# Page1.net
KiCad netlist of a schematic drawn in Altium Designer
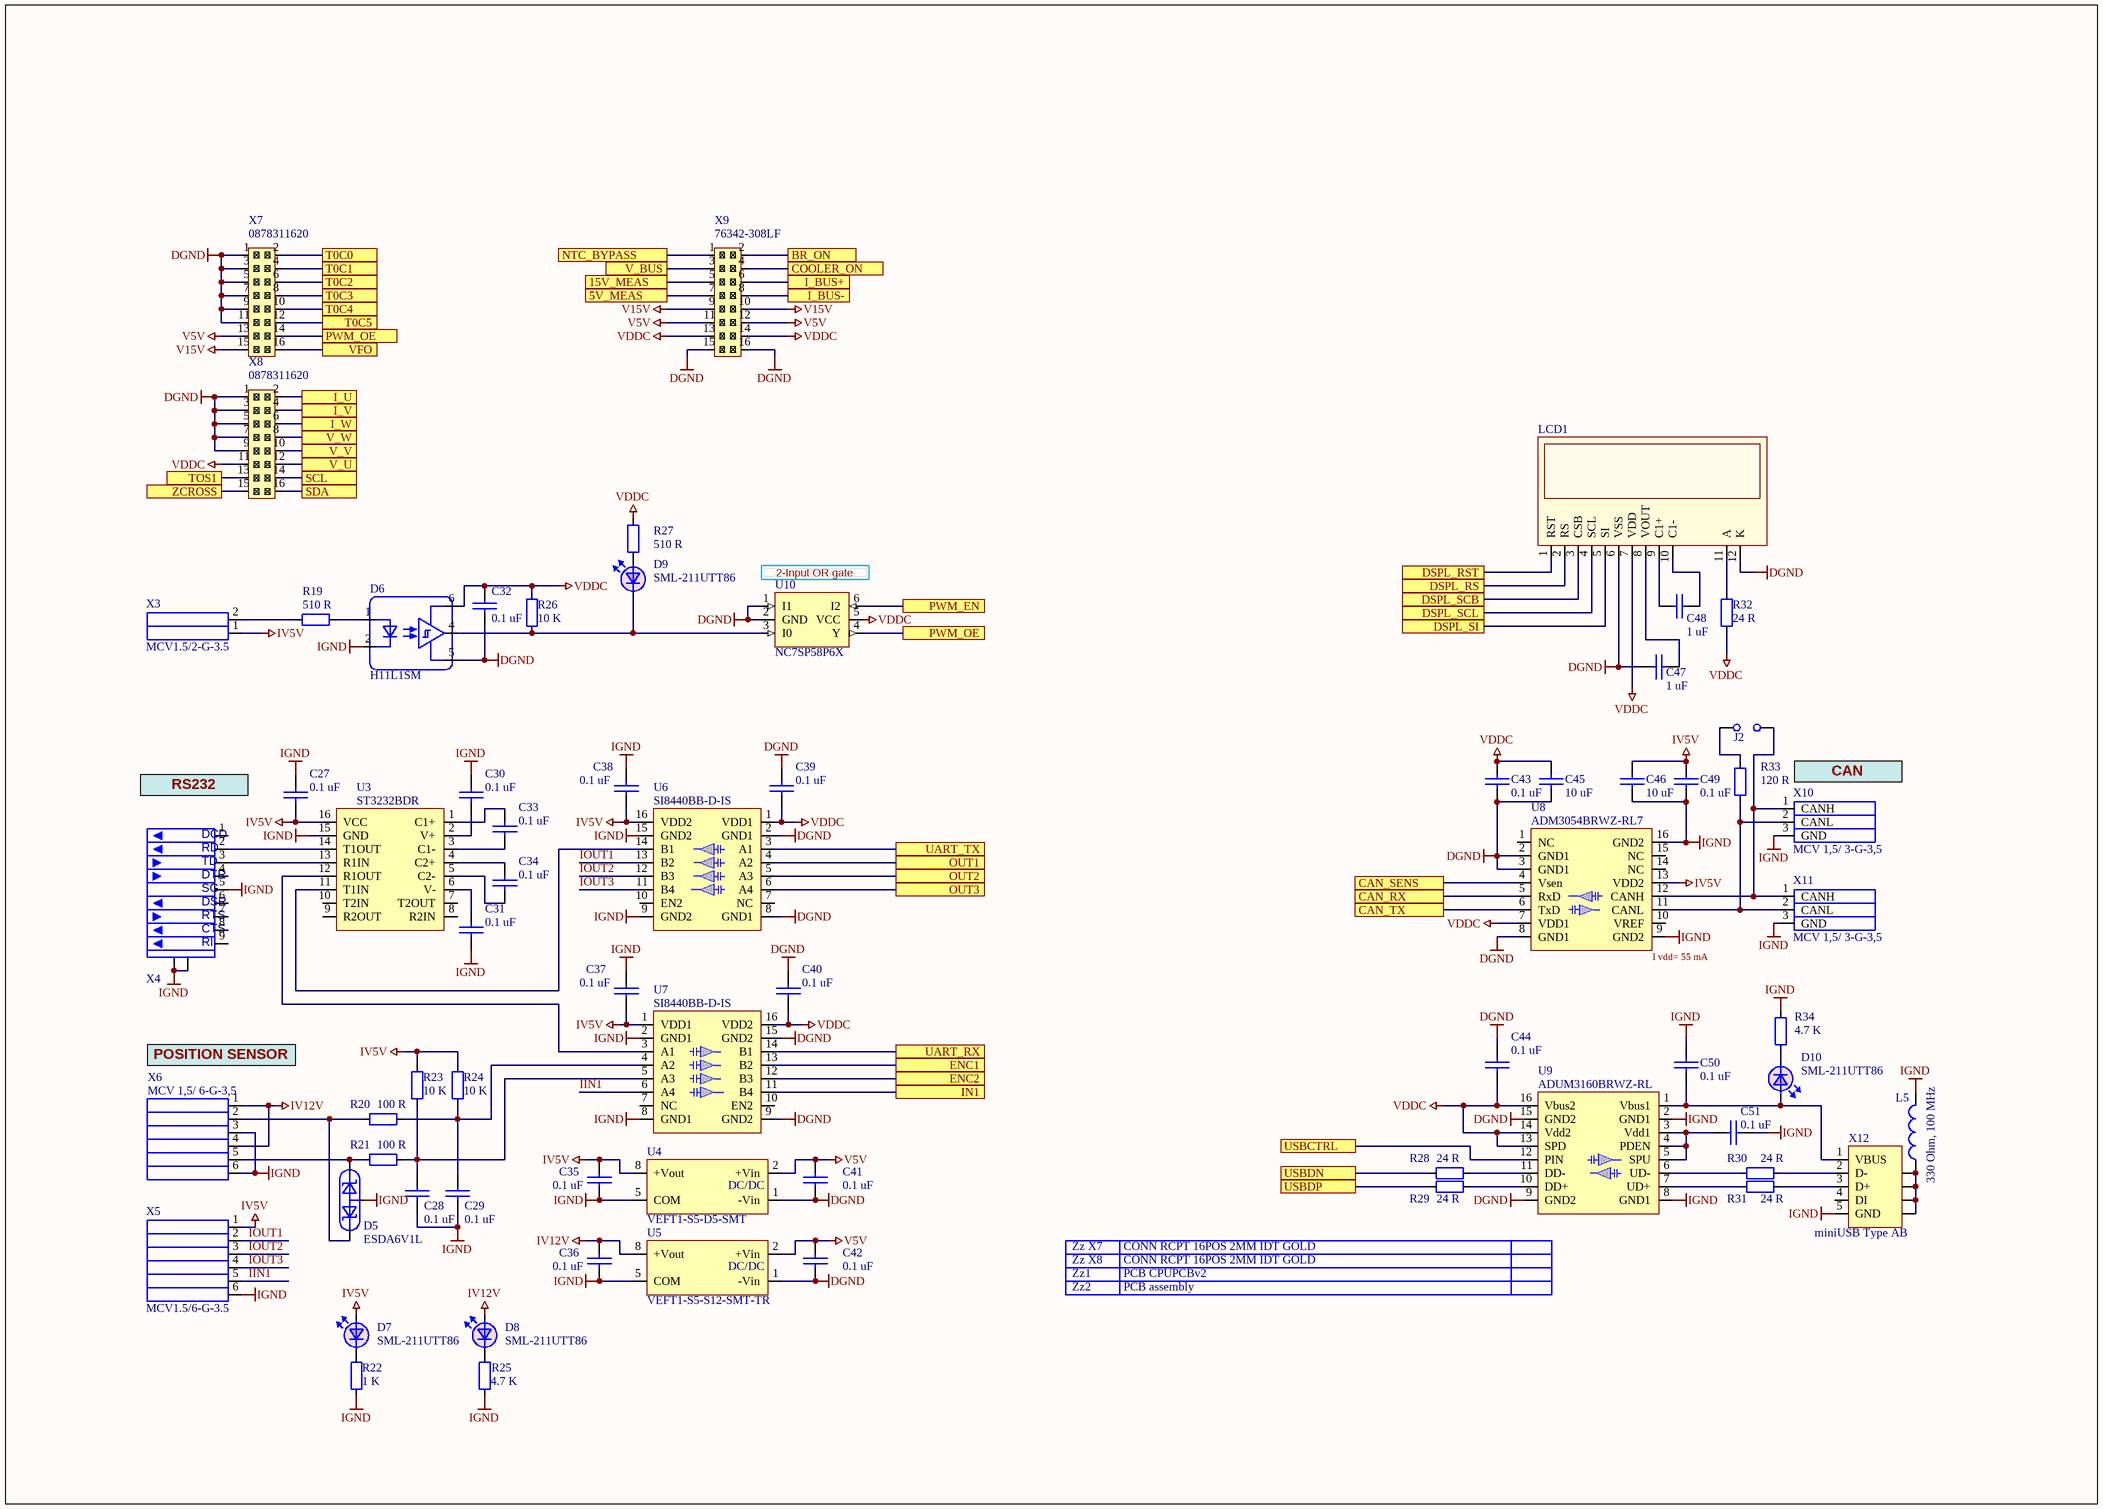
[diagram p0: Page1.SchDoc]

(export (version "E")
  (design (tool "Eeschema 10.0.6"))
  (components
    (comp (ref "C27")
      (value "0.1 uF")
      (footprint "1608[0603]")
      (description "0.1 uF, 25V, 10% , X7R,  0603 SMD MLC Capacitor")
      (fields (field (name "TOLERANCE") "10%") (field (name "MANUFACTURER") "SAMSUNG"))
      (libsource (lib "ea_Capacitors") (part "CVNF100K0603-25"))
    )
    (comp (ref "C28")
      (value "0.1 uF")
      (footprint "1608[0603]")
      (description "0.1 uF, 25V, 10% , X7R,  0603 SMD MLC Capacitor")
      (fields (field (name "TOLERANCE") "10%") (field (name "MANUFACTURER") "SAMSUNG"))
      (libsource (lib "ea_Capacitors") (part "CVNF100K0603-25"))
    )
    (comp (ref "C29")
      (value "0.1 uF")
      (footprint "1608[0603]")
      (description "0.1 uF, 25V, 10% , X7R,  0603 SMD MLC Capacitor")
      (fields (field (name "TOLERANCE") "10%") (field (name "MANUFACTURER") "SAMSUNG"))
      (libsource (lib "ea_Capacitors") (part "CVNF100K0603-25"))
    )
    (comp (ref "C30")
      (value "0.1 uF")
      (footprint "1608[0603]")
      (description "0.1 uF, 25V, 10% , X7R,  0603 SMD MLC Capacitor")
      (fields (field (name "TOLERANCE") "10%") (field (name "MANUFACTURER") "SAMSUNG"))
      (libsource (lib "ea_Capacitors") (part "CVNF100K0603-25"))
    )
    (comp (ref "C31")
      (value "0.1 uF")
      (footprint "1608[0603]")
      (description "0.1 uF, 25V, 10% , X7R,  0603 SMD MLC Capacitor")
      (fields (field (name "TOLERANCE") "10%") (field (name "MANUFACTURER") "SAMSUNG"))
      (libsource (lib "ea_Capacitors") (part "CVNF100K0603-25"))
    )
    (comp (ref "C32")
      (value "0.1 uF")
      (footprint "1608[0603]")
      (description "0.1 uF, 25V, 10% , X7R,  0603 SMD MLC Capacitor")
      (fields (field (name "TOLERANCE") "10%") (field (name "MANUFACTURER") "SAMSUNG"))
      (libsource (lib "ea_Capacitors") (part "CVNF100K0603-25"))
    )
    (comp (ref "C33")
      (value "0.1 uF")
      (footprint "1608[0603]")
      (description "0.1 uF, 25V, 10% , X7R,  0603 SMD MLC Capacitor")
      (fields (field (name "TOLERANCE") "10%") (field (name "MANUFACTURER") "SAMSUNG"))
      (libsource (lib "ea_Capacitors") (part "CVNF100K0603-25"))
    )
    (comp (ref "C34")
      (value "0.1 uF")
      (footprint "1608[0603]")
      (description "0.1 uF, 25V, 10% , X7R,  0603 SMD MLC Capacitor")
      (fields (field (name "TOLERANCE") "10%") (field (name "MANUFACTURER") "SAMSUNG"))
      (libsource (lib "ea_Capacitors") (part "CVNF100K0603-25"))
    )
    (comp (ref "C35")
      (value "0.1 uF")
      (footprint "1608[0603]")
      (description "0.1 uF, 25V, 10% , X7R,  0603 SMD MLC Capacitor")
      (fields (field (name "TOLERANCE") "10%") (field (name "MANUFACTURER") "SAMSUNG"))
      (libsource (lib "ea_Capacitors") (part "CVNF100K0603-25"))
    )
    (comp (ref "C36")
      (value "0.1 uF")
      (footprint "1608[0603]")
      (description "0.1 uF, 25V, 10% , X7R,  0603 SMD MLC Capacitor")
      (fields (field (name "TOLERANCE") "10%") (field (name "MANUFACTURER") "SAMSUNG"))
      (libsource (lib "ea_Capacitors") (part "CVNF100K0603-25"))
    )
    (comp (ref "C37")
      (value "0.1 uF")
      (footprint "1608[0603]")
      (description "0.1 uF, 25V, 10% , X7R,  0603 SMD MLC Capacitor")
      (fields (field (name "TOLERANCE") "10%") (field (name "MANUFACTURER") "SAMSUNG"))
      (libsource (lib "ea_Capacitors") (part "CVNF100K0603-25"))
    )
    (comp (ref "C38")
      (value "0.1 uF")
      (footprint "1608[0603]")
      (description "0.1 uF, 25V, 10% , X7R,  0603 SMD MLC Capacitor")
      (fields (field (name "TOLERANCE") "10%") (field (name "MANUFACTURER") "SAMSUNG"))
      (libsource (lib "ea_Capacitors") (part "CVNF100K0603-25"))
    )
    (comp (ref "C39")
      (value "0.1 uF")
      (footprint "1608[0603]")
      (description "0.1 uF, 25V, 10% , X7R,  0603 SMD MLC Capacitor")
      (fields (field (name "TOLERANCE") "10%") (field (name "MANUFACTURER") "SAMSUNG"))
      (libsource (lib "ea_Capacitors") (part "CVNF100K0603-25"))
    )
    (comp (ref "C40")
      (value "0.1 uF")
      (footprint "1608[0603]")
      (description "0.1 uF, 25V, 10% , X7R,  0603 SMD MLC Capacitor")
      (fields (field (name "TOLERANCE") "10%") (field (name "MANUFACTURER") "SAMSUNG"))
      (libsource (lib "ea_Capacitors") (part "CVNF100K0603-25"))
    )
    (comp (ref "C41")
      (value "0.1 uF")
      (footprint "1608[0603]")
      (description "0.1 uF, 25V, 10% , X7R,  0603 SMD MLC Capacitor")
      (fields (field (name "TOLERANCE") "10%") (field (name "MANUFACTURER") "SAMSUNG"))
      (libsource (lib "ea_Capacitors") (part "CVNF100K0603-25"))
    )
    (comp (ref "C42")
      (value "0.1 uF")
      (footprint "1608[0603]")
      (description "0.1 uF, 25V, 10% , X7R,  0603 SMD MLC Capacitor")
      (fields (field (name "TOLERANCE") "10%") (field (name "MANUFACTURER") "SAMSUNG"))
      (libsource (lib "ea_Capacitors") (part "CVNF100K0603-25"))
    )
    (comp (ref "C43")
      (value "0.1 uF")
      (footprint "1608[0603]")
      (description "0.1 uF, 25V, 10% , X7R,  0603 SMD MLC Capacitor")
      (fields (field (name "TOLERANCE") "10%") (field (name "MANUFACTURER") "SAMSUNG"))
      (libsource (lib "ea_Capacitors") (part "CVNF100K0603-25"))
    )
    (comp (ref "C44")
      (value "0.1 uF")
      (footprint "1608[0603]")
      (description "0.1 uF, 25V, 10% , X7R,  0603 SMD MLC Capacitor")
      (fields (field (name "TOLERANCE") "10%") (field (name "MANUFACTURER") "SAMSUNG"))
      (libsource (lib "ea_Capacitors") (part "CVNF100K0603-25"))
    )
    (comp (ref "C45")
      (value "10 uF")
      (footprint "2012[0805]")
      (description "10 uF, 16V, X5R, ±10%, 0805")
      (fields (field (name "MANUFACTURER") "TDK Corporation") (field (name "TOLERANCE") "±10%"))
      (libsource (lib "ea_Capacitors") (part "C2012X5R1C106K/0.85"))
    )
    (comp (ref "C46")
      (value "10 uF")
      (footprint "2012[0805]")
      (description "10 uF, 16V, X5R, ±10%, 0805")
      (fields (field (name "MANUFACTURER") "TDK Corporation") (field (name "TOLERANCE") "±10%"))
      (libsource (lib "ea_Capacitors") (part "C2012X5R1C106K/0.85"))
    )
    (comp (ref "C47")
      (value "1 uF")
      (footprint "2012[0805]")
      (description "1 uF, 16V, 10%, X7R, 0805")
      (fields (field (name "MANUFACTURER") "Kemet, Rohm, Darfon") (field (name "TOLERANCE") "10%"))
      (libsource (lib "ea_Capacitors") (part "CVUF001K0805"))
    )
    (comp (ref "C48")
      (value "1 uF")
      (footprint "2012[0805]")
      (description "1 uF, 16V, 10%, X7R, 0805")
      (fields (field (name "MANUFACTURER") "Kemet, Rohm, Darfon") (field (name "TOLERANCE") "10%"))
      (libsource (lib "ea_Capacitors") (part "CVUF001K0805"))
    )
    (comp (ref "C49")
      (value "0.1 uF")
      (footprint "1608[0603]")
      (description "0.1 uF, 25V, 10% , X7R,  0603 SMD MLC Capacitor")
      (fields (field (name "TOLERANCE") "10%") (field (name "MANUFACTURER") "SAMSUNG"))
      (libsource (lib "ea_Capacitors") (part "CVNF100K0603-25"))
    )
    (comp (ref "C50")
      (value "0.1 uF")
      (footprint "1608[0603]")
      (description "0.1 uF, 25V, 10% , X7R,  0603 SMD MLC Capacitor")
      (fields (field (name "TOLERANCE") "10%") (field (name "MANUFACTURER") "SAMSUNG"))
      (libsource (lib "ea_Capacitors") (part "CVNF100K0603-25"))
    )
    (comp (ref "C51")
      (value "0.1 uF")
      (footprint "1608[0603]")
      (description "0.1 uF, 25V, 10% , X7R,  0603 SMD MLC Capacitor")
      (fields (field (name "TOLERANCE") "10%") (field (name "MANUFACTURER") "SAMSUNG"))
      (libsource (lib "ea_Capacitors") (part "CVNF100K0603-25"))
    )
    (comp (ref "D5")
      (value "ESDA6V1L")
      (footprint "SOT23")
      (description "Dual transil array for ESD, 6.1 V, 300 W")
      (fields (field (name "MANUFACTURER") "Micro Commercial Co") (field (name "PARTNUM") "ESDA6V1L-TPCT-ND"))
      (libsource (lib "*") (part "ESDA6V1L"))
    )
    (comp (ref "D6")
      (value "H11L1SM")
      (footprint "DIP-6 SMD")
      (description "Optocoupler, SMD, 7500V,  1 Mbit, 1.6 mA")
      (fields
        (field (name "MANUFACTURER") "Fairchild Optoelectronics Group")
        (field (name "PARTNUM") "H11L1SM-ND")
      )
      (libsource (lib "ea_Opto") (part "H11L1SM"))
    )
    (comp (ref "D7")
      (value "SML-211UTT86")
      (footprint "0805 LED")
      (description "0805 red LED, hibright, 2 mA, 1.8V, 130°")
      (fields (field (name "MANUFACTURER") "Rohm") (field (name "PARTNUM") "511-1292-1-ND"))
      (libsource (lib "ea_Indicators") (part "SML-211UTT86"))
    )
    (comp (ref "D8")
      (value "SML-211UTT86")
      (footprint "0805 LED")
      (description "0805 red LED, hibright, 2 mA, 1.8V, 130°")
      (fields (field (name "MANUFACTURER") "Rohm") (field (name "PARTNUM") "511-1292-1-ND"))
      (libsource (lib "ea_Indicators") (part "SML-211UTT86"))
    )
    (comp (ref "D9")
      (value "SML-211UTT86")
      (footprint "0805 LED")
      (description "0805 red LED, hibright, 2 mA, 1.8V, 130°")
      (fields (field (name "MANUFACTURER") "Rohm") (field (name "PARTNUM") "511-1292-1-ND"))
      (libsource (lib "ea_Indicators") (part "SML-211UTT86"))
    )
    (comp (ref "D10")
      (value "SML-211UTT86")
      (footprint "0805 LED")
      (description "0805 red LED, hibright, 2 mA, 1.8V, 130°")
      (fields (field (name "MANUFACTURER") "Rohm") (field (name "PARTNUM") "511-1292-1-ND"))
      (libsource (lib "ea_Indicators") (part "SML-211UTT86"))
    )
    (comp (ref "J2")
      (value "PH1-02-TA-HT")
      (footprint "HDR1X2V")
      (description "2 Pos. 2.54 mm Single Row Through Hole Straight Pin Header")
      (fields (field (name "MANUFACTURER") "ADAM TECH"))
      (libsource (lib "ea_Commutation") (part "Jumper"))
    )
    (comp (ref "L5")
      (value "330 Ohm, 100 MHz")
      (footprint "0603")
      (description "Ferrite bead, 330 Ohm, 100 MHz,  1.5 A, 0.07 Ohm")
      (fields
        (field (name "MANUFACTURER") "Murata Electronics North America")
        (field (name "PARTNUM") "BLM18SG331TN1D")
      )
      (libsource (lib "*") (part "BLM18SG331TN1D"))
    )
    (comp (ref "LCD1")
      (value "NHD-C0216CZ-FSW-FBW-3V3")
      (footprint "Display NHD-C0216CZ-FSW-FBW-3V3")
      (description "LCD COG CHAR 2X16 WHT TRANSFL")
      (fields
        (field (name "MANUFACTURER") "Newhaven Display Intl")
        (field (name "PARTNUM") "NHD-C0216CZ-FSW-FBW-3V3-ND")
      )
      (libsource (lib "ea_LCD") (part "NHD-C0216CZ-FSW-FBW-3V3"))
    )
    (comp (ref "R19")
      (value "510 R")
      (footprint "0603")
      (description "510 R, 1%, 0603, SMD Resistor, Taped")
      (fields (field (name "MANUFACTURER") "Vishay") (field (name "TOLERANCE") "1%"))
      (libsource (lib "ea_Resistors") (part "RL0603E510-1"))
    )
    (comp (ref "R20")
      (value "100 R")
      (footprint "0603")
      (description "100 R, 1%, 0603, SMD Resistor, Taped")
      (fields (field (name "MANUFACTURER") "PANASONIC") (field (name "TOLERANCE") "1%"))
      (libsource (lib "ea_Resistors") (part "RL0603E100-1_1"))
    )
    (comp (ref "R21")
      (value "100 R")
      (footprint "0603")
      (description "100 R, 1%, 0603, SMD Resistor, Taped")
      (fields (field (name "MANUFACTURER") "PANASONIC") (field (name "TOLERANCE") "1%"))
      (libsource (lib "ea_Resistors") (part "RL0603E100-1_1"))
    )
    (comp (ref "R22")
      (value "1 K")
      (footprint "0603")
      (description "1 K, 1%, 0603, SMD Resistor, Taped")
      (fields (field (name "MANUFACTURER") "YAGEO AMERICA CORPORATION") (field (name "TOLERANCE") "1%"))
      (libsource (lib "ea_Resistors") (part "RL0603K001-1_1"))
    )
    (comp (ref "R23")
      (value "10 K")
      (footprint "0603")
      (description "10 K, 1%, 0603, SMD Resistor, Taped")
      (fields (field (name "MANUFACTURER") "PANASONIC") (field (name "TOLERANCE") "1%"))
      (libsource (lib "ea_Resistors") (part "RL0603K010-1"))
    )
    (comp (ref "R24")
      (value "10 K")
      (footprint "0603")
      (description "10 K, 1%, 0603, SMD Resistor, Taped")
      (fields (field (name "MANUFACTURER") "PANASONIC") (field (name "TOLERANCE") "1%"))
      (libsource (lib "ea_Resistors") (part "RL0603K010-1"))
    )
    (comp (ref "R25")
      (value "4.7 K")
      (footprint "0603")
      (description "4.7 K, 1%, 0603, SMD Resistor, Taped")
      (fields (field (name "MANUFACTURER") "YAGEO AMERICA CORPORATION") (field (name "TOLERANCE") "1%"))
      (libsource (lib "ea_Resistors") (part "RL0603K004.7-1_1"))
    )
    (comp (ref "R26")
      (value "10 K")
      (footprint "0603")
      (description "10 K, 1%, 0603, SMD Resistor, Taped")
      (fields (field (name "MANUFACTURER") "PANASONIC") (field (name "TOLERANCE") "1%"))
      (libsource (lib "ea_Resistors") (part "RL0603K010-1"))
    )
    (comp (ref "R27")
      (value "510 R")
      (footprint "0603")
      (description "510 R, 1%, 0603, SMD Resistor, Taped")
      (fields (field (name "MANUFACTURER") "Vishay") (field (name "TOLERANCE") "1%"))
      (libsource (lib "") (part "RL0603E510-1_1"))
    )
    (comp (ref "R28")
      (value "24 R")
      (footprint "0603")
      (description "24 R, 1%, 0603, SMD Resistor, Taped")
      (fields (field (name "MANUFACTURER") "YAGEO AMERICA CORPORATION") (field (name "TOLERANCE") "1%"))
      (libsource (lib "") (part "RL0603E024-1_1_2"))
    )
    (comp (ref "R29")
      (value "24 R")
      (footprint "0603")
      (description "24 R, 1%, 0603, SMD Resistor, Taped")
      (fields (field (name "MANUFACTURER") "YAGEO AMERICA CORPORATION") (field (name "TOLERANCE") "1%"))
      (libsource (lib "") (part "RL0603E024-1_1_1"))
    )
    (comp (ref "R30")
      (value "24 R")
      (footprint "0603")
      (description "24 R, 1%, 0603, SMD Resistor, Taped")
      (fields (field (name "MANUFACTURER") "YAGEO AMERICA CORPORATION") (field (name "TOLERANCE") "1%"))
      (libsource (lib "") (part "RL0603E024-1_1_2"))
    )
    (comp (ref "R31")
      (value "24 R")
      (footprint "0603")
      (description "24 R, 1%, 0603, SMD Resistor, Taped")
      (fields (field (name "MANUFACTURER") "YAGEO AMERICA CORPORATION") (field (name "TOLERANCE") "1%"))
      (libsource (lib "") (part "RL0603E024-1_1_1"))
    )
    (comp (ref "R32")
      (value "24 R")
      (footprint "0603")
      (description "24 R, 1%, 0603, SMD Resistor, Taped")
      (fields (field (name "MANUFACTURER") "YAGEO AMERICA CORPORATION") (field (name "TOLERANCE") "1%"))
      (libsource (lib "ea_Resistors") (part "RL0603E024-1_1"))
    )
    (comp (ref "R33")
      (value "120 R")
      (footprint "0603")
      (description "120 R, 1%, 0603, SMD Resistor, Taped")
      (fields (field (name "MANUFACTURER") "Vishay") (field (name "TOLERANCE") "1%"))
      (libsource (lib "ea_Resistors") (part "RL0603E120-1"))
    )
    (comp (ref "R34")
      (value "4.7 K")
      (footprint "0603")
      (description "4.7 K, 1%, 0603, SMD Resistor, Taped")
      (fields (field (name "MANUFACTURER") "YAGEO AMERICA CORPORATION") (field (name "TOLERANCE") "1%"))
      (libsource (lib "") (part "RL0603K004.7-1_1_1"))
    )
    (comp (ref "U3")
      (value "ST3232BDR")
      (footprint "R-16N, AnalogDev SO-16")
      (description "Low Power, 3.3 V, RS-232 Line Drivers/Receivers, 16-pin TSSOP16")
      (fields (field (name "MANUFACTURER") "ST"))
      (libsource (lib "*") (part "ST3232BDR"))
    )
    (comp (ref "U4")
      (value "VEFT1-S5-D5-SMT")
      (footprint "VEFT1_Sx_Dx_SMT")
      (description "DC/DC 5V In 5V Out,  1W, -40..+85 C, 3KV")
      (fields (field (name "MANUFACTURER") "CUI Inc") (field (name "PARTNUM") "102-2123-1-ND"))
      (libsource (lib "ea_PowerSources") (part "VEFT1-S5-D5-SMT"))
    )
    (comp (ref "U5")
      (value "VEFT1-S5-S12-SMT-TR")
      (footprint "VEFT1_Sx_Dx_SMT")
      (description "DC/DC 5V In 12V Out,  1W, -40..+85 C, 3KV")
      (fields (field (name "MANUFACTURER") "CUI Inc") (field (name "PARTNUM") "102-2132-1-ND"))
      (libsource (lib "ea_PowerSources") (part "VEFT1-S5-S12-SMT-TR"))
    )
    (comp (ref "U6")
      (value "SI8440BB-D-IS")
      (footprint "SO-G16/D10.4")
      (description "IC ISOLATOR 4CH 5.5V 16-SOIC")
      (fields
        (field (name "MANUFACTURER") "Silicon Laboratories Inc")
        (field (name "PARTNUM") "336-1760-5-ND")
      )
      (libsource (lib "ea_IC_Interfaces") (part "SI8440AB-D-IS"))
    )
    (comp (ref "U7")
      (value "SI8440BB-D-IS")
      (footprint "SO-G16/D10.4")
      (description "IC ISOLATOR 4CH 5.5V 16-SOIC")
      (fields
        (field (name "MANUFACTURER") "Silicon Laboratories Inc")
        (field (name "PARTNUM") "336-1760-5-ND")
      )
      (libsource (lib "") (part "SI8440AB-D-IS_1"))
    )
    (comp (ref "U8")
      (value "ADM3054BRWZ-RL7")
      (footprint "SO-G16/D10.4")
      (description "IC Isol TXRX CAN HS 16SOIC")
      (fields (field (name "MANUFACTURER") "Analog Divices") (field (name "PARTNUM") "ADM3054BRWZ-RL7CT-ND"))
      (libsource (lib "ea_IC_Interfaces") (part "ADM3054BRWZ-RL7"))
    )
    (comp (ref "U9")
      (value "ADUM3160BRWZ-RL")
      (footprint "SO-G16/D10.4")
      (description "IC Isol USB 2.5K 16SOIC")
      (fields (field (name "MANUFACTURER") "Analog Divices") (field (name "PARTNUM") "ADUM3160BRWZ-RLCT-ND"))
      (libsource (lib "ea_IC_Interfaces") (part "ADUM3160BRWZ-RL"))
    )
    (comp (ref "U10")
      (value "NC7SP58P6X")
      (footprint "SOT363")
      (description "IC GATE ULP UNIV 2-INP SOT363")
      (fields (field (name "MANUFACTURER") "TEXAS INSTRUMENTS") (field (name "PARTNUM") "NC7SP58P6XCT-ND"))
      (libsource (lib "ea_IC_Logic") (part "NC7SP58P6X"))
    )
    (comp (ref "X3")
      (value "MCV1.5/2-G-3.5")
      (footprint "mcv1.5-2-g_3.5")
      (description "HEADER, VERTICAL, 3.5MM, 2WAY")
      (fields (field (name "MANUFACTURER") "PHOENIX CONTACT") (field (name "PARTNUM") "3704816"))
      (libsource (lib "ea_Connectors") (part "MCV1.5/2-G-3.5"))
    )
    (comp (ref "X4")
      (value "DB9V_1-1634222-2")
      (footprint "DB9 vertical")
      (description "AMP - 1-1634222-2 - SOCKET, D, PCB, THR/INSERT, 9WAY")
      (fields (field (name "MANUFACTURER") "TYCO ELECTRONICS / AMP") (field (name "PARTNUM") "5082018"))
      (libsource (lib "ea_Connectors") (part "DB9V_1-1634222-2"))
    )
    (comp (ref "X5")
      (value "MCV1.5/6-G-3.5")
      (footprint "mcv1.5-6-g_3.5")
      (description "HEADER, VERTICAL, 3.5MM, 6WAY")
      (fields (field (name "MANUFACTURER") "PHOENIX CONTACT") (field (name "PARTNUM") "3704853"))
      (libsource (lib "ea_Connectors") (part "MCV1.5/6-G-3.5"))
    )
    (comp (ref "X6")
      (value "MCV 1,5/ 6-G-3,5")
      (footprint "mcv1.5-6-g_3.5")
      (description "HEADER, VERTICAL, 3.5MM, 6WAY")
      (fields (field (name "MANUFACTURER") "PHOENIX CONTACT") (field (name "PARTNUM") "1843648"))
      (libsource (lib "ea_Connectors") (part "MCV1.5/6-G-3.5"))
    )
    (comp (ref "X7")
      (value "0878311620")
      (footprint "8x2, 2.00mm Pitch Milli-Grid™ Header, Molex")
      (description "CONN HEADER 16POS 2MM VERT GOLD")
      (fields (field (name "MANUFACTURER") "Molex") (field (name "PARTNUM") "WM18562-ND"))
      (libsource (lib "ea_Connectors") (part "0878311620"))
    )
    (comp (ref "X8")
      (value "0878311620")
      (footprint "8x2, 2.00mm Pitch Milli-Grid™ Header, Molex")
      (description "CONN HEADER 16POS 2MM VERT GOLD")
      (fields (field (name "MANUFACTURER") "Molex") (field (name "PARTNUM") "WM18562-ND"))
      (libsource (lib "ea_Connectors") (part "0878311620"))
    )
    (comp (ref "X9")
      (value "76342-308LF")
      (footprint "76342-308LF")
      (description "Board to Board & Mezzanine Connectors 16P VRT DR RECEPT .76 GOLD")
      (fields (field (name "MANUFACTURER") "FCI") (field (name "PARTNUM") "649-76342-308LF"))
      (libsource (lib "Inverter_v2") (part "76342-308LF"))
    )
    (comp (ref "X10")
      (value "MCV 1,5/ 3-G-3,5")
      (footprint "mcv1.5-3-g_3.5")
      (description "HEADER, VERTICAL, 3.5MM, 3WAY")
      (fields (field (name "MANUFACTURER") "PHOENIX CONTACT") (field (name "PARTNUM") "1843619"))
      (libsource (lib "ea_Connectors") (part "MCV1.5/3-G-3.5"))
    )
    (comp (ref "X11")
      (value "MCV 1,5/ 3-G-3,5")
      (footprint "mcv1.5-3-g_3.5")
      (description "HEADER, VERTICAL, 3.5MM, 3WAY")
      (fields (field (name "MANUFACTURER") "PHOENIX CONTACT") (field (name "PARTNUM") "1843619"))
      (libsource (lib "ea_Connectors") (part "MCV1.5/3-G-3.5"))
    )
    (comp (ref "X12")
      (value "miniUSB Type AB")
      (footprint "USB AB 56579-0576 Molex")
      (description "SMD USB - OTG, miniUSB Type AB")
      (fields
        (field (name "MANUFACTURER") "Molex/Waldom Electronics Corp")
        (field (name "PARTNUM") "WM17122CT-ND")
      )
      (libsource (lib "ea_Connectors") (part "USB AB 56579-0576"))
    )
    (comp (ref "Zz X7")
      (value "CONN RCPT 16POS 2MM IDT GOLD")
      (fields (field (name "MANUFACTURER") "Molex Inc") (field (name "PARTNUM") "WM8606-ND"))
      (libsource (lib "ea_Mechanical") (part "BOM item"))
    )
    (comp (ref "Zz X8")
      (value "CONN RCPT 16POS 2MM IDT GOLD")
      (fields (field (name "MANUFACTURER") "Molex Inc") (field (name "PARTNUM") "WM8606-ND"))
      (libsource (lib "ea_Mechanical") (part "BOM item"))
    )
    (comp (ref "Zz1")
      (value "PCB CPUPCBv2")
      (fields (field (name "MANUFACTURER") "Brandner") (field (name "PARTNUM") "CPUPCBv2 board"))
      (libsource (lib "ea_Mechanical") (part "BOM item"))
    )
    (comp (ref "Zz2")
      (value "PCB assembly")
      (fields (field (name "MANUFACTURER") "ESEMDA") (field (name "PARTNUM") "CPUPCBv2 assembly"))
      (libsource (lib "ea_Mechanical") (part "BOM item"))
    )
  )
  (nets
    (net (code "1") (name "/5V_MEAS") (class "Default")
      (node (ref "X9") (pin "7") (pinfunction "7_7") (pintype "passive"))
    )
    (net (code "2") (name "/15V_MEAS") (class "Default")
      (node (ref "X9") (pin "5") (pinfunction "5_5") (pintype "passive"))
    )
    (net (code "3") (name "/BR_ON") (class "Default")
      (node (ref "X9") (pin "2") (pinfunction "2_2") (pintype "passive"))
    )
    (net (code "4") (name "/CAN_RX") (class "Default")
      (node (ref "U8") (pin "5") (pinfunction "RxD_5") (pintype "passive"))
    )
    (net (code "5") (name "/CAN_SENS") (class "Default")
      (node (ref "U8") (pin "4") (pinfunction "Vsen_4") (pintype "passive"))
    )
    (net (code "6") (name "/CAN_TX") (class "Default")
      (node (ref "U8") (pin "6") (pinfunction "TxD_6") (pintype "passive"))
    )
    (net (code "7") (name "/COOLER_ON") (class "Default")
      (node (ref "X9") (pin "4") (pinfunction "4_4") (pintype "passive"))
    )
    (net (code "8") (name "/DSPL_RS") (class "Default")
      (node (ref "LCD1") (pin "2") (pinfunction "RS_2") (pintype "passive"))
    )
    (net (code "9") (name "/DSPL_RST") (class "Default")
      (node (ref "LCD1") (pin "1") (pinfunction "RST_1") (pintype "passive"))
    )
    (net (code "10") (name "/DSPL_SCB") (class "Default")
      (node (ref "LCD1") (pin "3") (pinfunction "CSB_3") (pintype "passive"))
    )
    (net (code "11") (name "/DSPL_SCL") (class "Default")
      (node (ref "LCD1") (pin "4") (pinfunction "SCL_4") (pintype "passive"))
    )
    (net (code "12") (name "/DSPL_SI") (class "Default")
      (node (ref "LCD1") (pin "5") (pinfunction "SI_5") (pintype "passive"))
    )
    (net (code "13") (name "/ENC1") (class "Default")
      (node (ref "U7") (pin "13") (pinfunction "B2_13") (pintype "passive"))
    )
    (net (code "14") (name "/ENC2") (class "Default")
      (node (ref "U7") (pin "12") (pinfunction "B3_12") (pintype "passive"))
    )
    (net (code "15") (name "/IIN1") (class "Default")
      (node (ref "U7") (pin "6") (pinfunction "A4_6") (pintype "passive"))
      (node (ref "X5") (pin "5") (pinfunction "5_5") (pintype "passive"))
    )
    (net (code "16") (name "/IN1") (class "Default")
      (node (ref "U7") (pin "11") (pinfunction "B4_11") (pintype "passive"))
    )
    (net (code "17") (name "/IOUT1") (class "Default")
      (node (ref "U6") (pin "13") (pinfunction "B2_13") (pintype "passive"))
      (node (ref "X5") (pin "2") (pinfunction "2_2") (pintype "passive"))
    )
    (net (code "18") (name "/IOUT2") (class "Default")
      (node (ref "U6") (pin "12") (pinfunction "B3_12") (pintype "passive"))
      (node (ref "X5") (pin "3") (pinfunction "3_3") (pintype "passive"))
    )
    (net (code "19") (name "/IOUT3") (class "Default")
      (node (ref "U6") (pin "11") (pinfunction "B4_11") (pintype "passive"))
      (node (ref "X5") (pin "4") (pinfunction "4_4") (pintype "passive"))
    )
    (net (code "20") (name "/I_BUS+") (class "Default")
      (node (ref "X9") (pin "6") (pinfunction "6_6") (pintype "passive"))
    )
    (net (code "21") (name "/I_BUS-") (class "Default")
      (node (ref "X9") (pin "8") (pinfunction "8_8") (pintype "passive"))
    )
    (net (code "22") (name "/I_U") (class "Default")
      (node (ref "X8") (pin "2") (pinfunction "2_2") (pintype "passive"))
    )
    (net (code "23") (name "/I_V") (class "Default")
      (node (ref "X8") (pin "4") (pinfunction "4_4") (pintype "passive"))
    )
    (net (code "24") (name "/I_W") (class "Default")
      (node (ref "X8") (pin "6") (pinfunction "6_6") (pintype "passive"))
    )
    (net (code "25") (name "/NTC_BYPASS") (class "Default")
      (node (ref "X9") (pin "1") (pinfunction "1_1") (pintype "passive"))
    )
    (net (code "26") (name "/OUT1") (class "Default")
      (node (ref "U6") (pin "4") (pinfunction "A2_4") (pintype "passive"))
    )
    (net (code "27") (name "/OUT2") (class "Default")
      (node (ref "U6") (pin "5") (pinfunction "A3_5") (pintype "passive"))
    )
    (net (code "28") (name "/OUT3") (class "Default")
      (node (ref "U6") (pin "6") (pinfunction "A4_6") (pintype "passive"))
    )
    (net (code "29") (name "/PWM_EN") (class "Default")
      (node (ref "U10") (pin "6") (pinfunction "I2_6") (pintype "input"))
    )
    (net (code "30") (name "/PWM_OE") (class "Default")
      (node (ref "U10") (pin "4") (pinfunction "Y_4") (pintype "output"))
      (node (ref "X7") (pin "14") (pinfunction "14_14") (pintype "passive"))
    )
    (net (code "31") (name "/SCL") (class "Default")
      (node (ref "X8") (pin "14") (pinfunction "14_14") (pintype "passive"))
    )
    (net (code "32") (name "/SDA") (class "Default")
      (node (ref "X8") (pin "16") (pinfunction "16_16") (pintype "passive"))
    )
    (net (code "33") (name "/T0C0") (class "Default")
      (node (ref "X7") (pin "2") (pinfunction "2_2") (pintype "passive"))
    )
    (net (code "34") (name "/T0C1") (class "Default")
      (node (ref "X7") (pin "4") (pinfunction "4_4") (pintype "passive"))
    )
    (net (code "35") (name "/T0C2") (class "Default")
      (node (ref "X7") (pin "6") (pinfunction "6_6") (pintype "passive"))
    )
    (net (code "36") (name "/T0C3") (class "Default")
      (node (ref "X7") (pin "8") (pinfunction "8_8") (pintype "passive"))
    )
    (net (code "37") (name "/T0C4") (class "Default")
      (node (ref "X7") (pin "10") (pinfunction "10_10") (pintype "passive"))
    )
    (net (code "38") (name "/T0C5") (class "Default")
      (node (ref "X7") (pin "12") (pinfunction "12_12") (pintype "passive"))
    )
    (net (code "39") (name "/TOS1") (class "Default")
      (node (ref "X8") (pin "13") (pinfunction "13_13") (pintype "passive"))
    )
    (net (code "40") (name "/UART_RX") (class "Default")
      (node (ref "U7") (pin "14") (pinfunction "B1_14") (pintype "passive"))
    )
    (net (code "41") (name "/UART_TX") (class "Default")
      (node (ref "U6") (pin "3") (pinfunction "A1_3") (pintype "passive"))
    )
    (net (code "42") (name "/USBCTRL") (class "Default")
      (node (ref "U9") (pin "12") (pinfunction "PIN_12") (pintype "passive"))
    )
    (net (code "43") (name "/USBDN") (class "Default")
      (node (ref "R28") (pin "2") (pinfunction "2_2") (pintype "passive"))
    )
    (net (code "44") (name "/USBDP") (class "Default")
      (node (ref "R29") (pin "1") (pinfunction "1_1") (pintype "passive"))
    )
    (net (code "45") (name "/VFO") (class "Default")
      (node (ref "X7") (pin "16") (pinfunction "16_16") (pintype "passive"))
    )
    (net (code "46") (name "/V_BUS") (class "Default")
      (node (ref "X9") (pin "3") (pinfunction "3_3") (pintype "passive"))
    )
    (net (code "47") (name "/V_U") (class "Default")
      (node (ref "X8") (pin "12") (pinfunction "12_12") (pintype "passive"))
    )
    (net (code "48") (name "/V_V") (class "Default")
      (node (ref "X8") (pin "10") (pinfunction "10_10") (pintype "passive"))
    )
    (net (code "49") (name "/V_W") (class "Default")
      (node (ref "X8") (pin "8") (pinfunction "8_8") (pintype "passive"))
    )
    (net (code "50") (name "/ZCROSS") (class "Default")
      (node (ref "X8") (pin "15") (pinfunction "15_15") (pintype "passive"))
    )
    (net (code "51") (name "DGND") (class "Default")
      (node (ref "C32") (pin "1") (pinfunction "1_1") (pintype "passive"))
      (node (ref "C39") (pin "2") (pinfunction "2_2") (pintype "passive"))
      (node (ref "C40") (pin "2") (pinfunction "2_2") (pintype "passive"))
      (node (ref "C41") (pin "1") (pinfunction "1_1") (pintype "passive"))
      (node (ref "C42") (pin "1") (pinfunction "1_1") (pintype "passive"))
      (node (ref "C43") (pin "1") (pinfunction "1_1") (pintype "passive"))
      (node (ref "C44") (pin "2") (pinfunction "2_2") (pintype "passive"))
      (node (ref "C45") (pin "2") (pinfunction "2_2") (pintype "passive"))
      (node (ref "C47") (pin "1") (pinfunction "1_1") (pintype "passive"))
      (node (ref "D6") (pin "5") (pinfunction "GND_5") (pintype "passive"))
      (node (ref "LCD1") (pin "12") (pinfunction "K_12") (pintype "passive"))
      (node (ref "LCD1") (pin "6") (pinfunction "VSS_6") (pintype "passive"))
      (node (ref "U10") (pin "1") (pinfunction "I1_1") (pintype "input"))
      (node (ref "U10") (pin "2") (pinfunction "GND_2") (pintype "power_in"))
      (node (ref "U4") (pin "1") (pinfunction "-Vin_1") (pintype "passive"))
      (node (ref "U5") (pin "1") (pinfunction "-Vin_1") (pintype "passive"))
      (node (ref "U6") (pin "2") (pinfunction "GND1_2") (pintype "passive"))
      (node (ref "U6") (pin "8") (pinfunction "GND1_8") (pintype "passive"))
      (node (ref "U7") (pin "15") (pinfunction "GND2_15") (pintype "passive"))
      (node (ref "U7") (pin "9") (pinfunction "GND2_9") (pintype "passive"))
      (node (ref "U8") (pin "2") (pinfunction "GND1_2") (pintype "passive"))
      (node (ref "U8") (pin "3") (pinfunction "GND1_3") (pintype "passive"))
      (node (ref "U8") (pin "8") (pinfunction "GND1_8") (pintype "passive"))
      (node (ref "U9") (pin "15") (pinfunction "GND2_15") (pintype "passive"))
      (node (ref "U9") (pin "9") (pinfunction "GND2_9") (pintype "passive"))
      (node (ref "X7") (pin "1") (pinfunction "1_1") (pintype "passive"))
      (node (ref "X7") (pin "11") (pinfunction "11_11") (pintype "passive"))
      (node (ref "X7") (pin "3") (pinfunction "3_3") (pintype "passive"))
      (node (ref "X7") (pin "5") (pinfunction "5_5") (pintype "passive"))
      (node (ref "X7") (pin "7") (pinfunction "7_7") (pintype "passive"))
      (node (ref "X7") (pin "9") (pinfunction "9_9") (pintype "passive"))
      (node (ref "X8") (pin "1") (pinfunction "1_1") (pintype "passive"))
      (node (ref "X8") (pin "3") (pinfunction "3_3") (pintype "passive"))
      (node (ref "X8") (pin "5") (pinfunction "5_5") (pintype "passive"))
      (node (ref "X8") (pin "7") (pinfunction "7_7") (pintype "passive"))
      (node (ref "X8") (pin "9") (pinfunction "9_9") (pintype "passive"))
      (node (ref "X9") (pin "15") (pinfunction "15_15") (pintype "passive"))
      (node (ref "X9") (pin "16") (pinfunction "16_16") (pintype "passive"))
    )
    (net (code "52") (name "IGND") (class "Default")
      (node (ref "C27") (pin "2") (pinfunction "2_2") (pintype "passive"))
      (node (ref "C28") (pin "1") (pinfunction "1_1") (pintype "passive"))
      (node (ref "C29") (pin "1") (pinfunction "1_1") (pintype "passive"))
      (node (ref "C30") (pin "2") (pinfunction "2_2") (pintype "passive"))
      (node (ref "C31") (pin "1") (pinfunction "1_1") (pintype "passive"))
      (node (ref "C35") (pin "1") (pinfunction "1_1") (pintype "passive"))
      (node (ref "C36") (pin "1") (pinfunction "1_1") (pintype "passive"))
      (node (ref "C37") (pin "2") (pinfunction "2_2") (pintype "passive"))
      (node (ref "C38") (pin "2") (pinfunction "2_2") (pintype "passive"))
      (node (ref "C46") (pin "2") (pinfunction "2_2") (pintype "passive"))
      (node (ref "C49") (pin "1") (pinfunction "1_1") (pintype "passive"))
      (node (ref "C50") (pin "2") (pinfunction "2_2") (pintype "passive"))
      (node (ref "C51") (pin "2") (pinfunction "2_2") (pintype "passive"))
      (node (ref "D5") (pin "3") (pintype "passive"))
      (node (ref "D6") (pin "2") (pinfunction "C_2") (pintype "passive"))
      (node (ref "L5") (pin "1") (pinfunction "1_1") (pintype "passive"))
      (node (ref "R22") (pin "1") (pinfunction "1_1") (pintype "passive"))
      (node (ref "R25") (pin "1") (pinfunction "1_1") (pintype "passive"))
      (node (ref "R34") (pin "1") (pinfunction "1_1") (pintype "passive"))
      (node (ref "U3") (pin "15") (pinfunction "GND_15") (pintype "passive"))
      (node (ref "U4") (pin "5") (pinfunction "COM_5") (pintype "passive"))
      (node (ref "U5") (pin "5") (pinfunction "COM_5") (pintype "passive"))
      (node (ref "U6") (pin "15") (pinfunction "GND2_15") (pintype "passive"))
      (node (ref "U6") (pin "9") (pinfunction "GND2_9") (pintype "passive"))
      (node (ref "U7") (pin "2") (pinfunction "GND1_2") (pintype "passive"))
      (node (ref "U7") (pin "8") (pinfunction "GND1_8") (pintype "passive"))
      (node (ref "U8") (pin "16") (pinfunction "GND2_16") (pintype "passive"))
      (node (ref "U8") (pin "9") (pinfunction "GND2_9") (pintype "passive"))
      (node (ref "U9") (pin "2") (pinfunction "GND1_2") (pintype "passive"))
      (node (ref "U9") (pin "8") (pinfunction "GND1_8") (pintype "passive"))
      (node (ref "X10") (pin "3") (pinfunction "GND_3") (pintype "passive"))
      (node (ref "X11") (pin "3") (pinfunction "GND_3") (pintype "passive"))
      (node (ref "X12") (pin "5") (pinfunction "GND_5") (pintype "power_in"))
      (node (ref "X4") (pin "10") (pinfunction "10_10") (pintype "passive"))
      (node (ref "X4") (pin "11") (pinfunction "11_11") (pintype "passive"))
      (node (ref "X4") (pin "5") (pinfunction "5_5") (pintype "passive"))
      (node (ref "X5") (pin "6") (pinfunction "6_6") (pintype "passive"))
      (node (ref "X6") (pin "3") (pinfunction "3_3") (pintype "passive"))
      (node (ref "X6") (pin "6") (pinfunction "6_6") (pintype "passive"))
    )
    (net (code "53") (name "IV5V") (class "Default")
      (node (ref "C27") (pin "1") (pinfunction "1_1") (pintype "passive"))
      (node (ref "C35") (pin "2") (pinfunction "2_2") (pintype "passive"))
      (node (ref "C37") (pin "1") (pinfunction "1_1") (pintype "passive"))
      (node (ref "C38") (pin "1") (pinfunction "1_1") (pintype "passive"))
      (node (ref "C46") (pin "1") (pinfunction "1_1") (pintype "passive"))
      (node (ref "C49") (pin "2") (pinfunction "2_2") (pintype "passive"))
      (node (ref "D7") (pin "1") (pinfunction "1_1") (pintype "passive"))
      (node (ref "R23") (pin "1") (pinfunction "1_1") (pintype "passive"))
      (node (ref "R24") (pin "1") (pinfunction "1_1") (pintype "passive"))
      (node (ref "U3") (pin "16") (pinfunction "VCC_16") (pintype "passive"))
      (node (ref "U4") (pin "8") (pinfunction "+Vout_8") (pintype "passive"))
      (node (ref "U6") (pin "16") (pinfunction "VDD2_16") (pintype "passive"))
      (node (ref "U7") (pin "1") (pinfunction "VDD1_1") (pintype "passive"))
      (node (ref "U8") (pin "13") (pinfunction "VDD2_13") (pintype "passive"))
      (node (ref "X3") (pin "1") (pinfunction "1_1") (pintype "passive"))
      (node (ref "X5") (pin "1") (pinfunction "1_1") (pintype "passive"))
    )
    (net (code "54") (name "IV12V") (class "Default")
      (node (ref "C36") (pin "2") (pinfunction "2_2") (pintype "passive"))
      (node (ref "D8") (pin "1") (pinfunction "1_1") (pintype "passive"))
      (node (ref "U5") (pin "8") (pinfunction "+Vout_8") (pintype "passive"))
      (node (ref "X6") (pin "1") (pinfunction "1_1") (pintype "passive"))
      (node (ref "X6") (pin "4") (pinfunction "4_4") (pintype "passive"))
    )
    (net (code "55") (name "Net-(D5-Pad1)") (class "Default")
      (node (ref "D5") (pin "1") (pintype "passive"))
      (node (ref "R21") (pin "2") (pinfunction "2_2") (pintype "passive"))
      (node (ref "X6") (pin "5") (pinfunction "5_5") (pintype "passive"))
    )
    (net (code "56") (name "Net-(D5-Pad2)") (class "Default")
      (node (ref "D5") (pin "2") (pintype "passive"))
      (node (ref "R20") (pin "2") (pinfunction "2_2") (pintype "passive"))
      (node (ref "X6") (pin "2") (pinfunction "2_2") (pintype "passive"))
    )
    (net (code "57") (name "Net-(D6-A)") (class "Default")
      (node (ref "D6") (pin "1") (pinfunction "A_1") (pintype "passive"))
      (node (ref "R19") (pin "1") (pinfunction "1_1") (pintype "passive"))
    )
    (net (code "58") (name "Net-(D6-OUT)") (class "Default")
      (node (ref "D6") (pin "4") (pinfunction "OUT_4") (pintype "passive"))
      (node (ref "D9") (pin "2") (pinfunction "2_2") (pintype "passive"))
      (node (ref "R26") (pin "2") (pinfunction "2_2") (pintype "passive"))
      (node (ref "U10") (pin "3") (pinfunction "I0_3") (pintype "input"))
    )
    (net (code "59") (name "Net-(D7-Pad2)") (class "Default")
      (node (ref "D7") (pin "2") (pinfunction "2_2") (pintype "passive"))
      (node (ref "R22") (pin "2") (pinfunction "2_2") (pintype "passive"))
    )
    (net (code "60") (name "Net-(D8-Pad2)") (class "Default")
      (node (ref "D8") (pin "2") (pinfunction "2_2") (pintype "passive"))
      (node (ref "R25") (pin "2") (pinfunction "2_2") (pintype "passive"))
    )
    (net (code "61") (name "Net-(D9-Pad1)") (class "Default")
      (node (ref "D9") (pin "1") (pinfunction "1_1") (pintype "passive"))
      (node (ref "R27") (pin "2") (pinfunction "2_2") (pintype "passive"))
    )
    (net (code "62") (name "Net-(D10-Pad2)") (class "Default")
      (node (ref "D10") (pin "2") (pinfunction "2_2") (pintype "passive"))
      (node (ref "R34") (pin "2") (pinfunction "2_2") (pintype "passive"))
    )
    (net (code "63") (name "Net-(J2-Pad2)") (class "Default")
      (node (ref "J2") (pin "2") (pinfunction "2_2") (pintype "passive"))
      (node (ref "R33") (pin "1") (pinfunction "1_1") (pintype "passive"))
    )
    (net (code "64") (name "Net-(L5-Pad2)") (class "Default")
      (node (ref "L5") (pin "2") (pinfunction "2_2") (pintype "passive"))
      (node (ref "X12") (pin "S1") (pinfunction "SHLD_S1") (pintype "passive"))
      (node (ref "X12") (pin "S2") (pinfunction "SHLD_S2") (pintype "passive"))
      (node (ref "X12") (pin "S3") (pinfunction "SHLD_S3") (pintype "passive"))
      (node (ref "X12") (pin "S4") (pinfunction "SHLD_S4") (pintype "passive"))
    )
    (net (code "65") (name "Net-(LCD1-A)") (class "Default")
      (node (ref "LCD1") (pin "11") (pinfunction "A_11") (pintype "passive"))
      (node (ref "R32") (pin "1") (pinfunction "1_1") (pintype "passive"))
    )
    (net (code "66") (name "Net-(LCD1-C1+)") (class "Default")
      (node (ref "C48") (pin "1") (pinfunction "1_1") (pintype "passive"))
      (node (ref "LCD1") (pin "9") (pinfunction "C1+_9") (pintype "passive"))
    )
    (net (code "67") (name "Net-(LCD1-C1-)") (class "Default")
      (node (ref "C48") (pin "2") (pinfunction "2_2") (pintype "passive"))
      (node (ref "LCD1") (pin "10") (pinfunction "C1-_10") (pintype "passive"))
    )
    (net (code "68") (name "Net-(LCD1-VOUT)") (class "Default")
      (node (ref "C47") (pin "2") (pinfunction "2_2") (pintype "passive"))
      (node (ref "LCD1") (pin "8") (pinfunction "VOUT_8") (pintype "passive"))
    )
    (net (code "69") (name "Net-(R19-Pad2)") (class "Default")
      (node (ref "R19") (pin "2") (pinfunction "2_2") (pintype "passive"))
      (node (ref "X3") (pin "2") (pinfunction "2_2") (pintype "passive"))
    )
    (net (code "70") (name "Net-(U3-C1+)") (class "Default")
      (node (ref "C33") (pin "2") (pinfunction "2_2") (pintype "passive"))
      (node (ref "U3") (pin "1") (pinfunction "C1+_1") (pintype "passive"))
    )
    (net (code "71") (name "Net-(U3-C1-)") (class "Default")
      (node (ref "C33") (pin "1") (pinfunction "1_1") (pintype "passive"))
      (node (ref "U3") (pin "3") (pinfunction "C1-_3") (pintype "passive"))
    )
    (net (code "72") (name "Net-(U3-C2+)") (class "Default")
      (node (ref "C34") (pin "2") (pinfunction "2_2") (pintype "passive"))
      (node (ref "U3") (pin "4") (pinfunction "C2+_4") (pintype "passive"))
    )
    (net (code "73") (name "Net-(U3-C2-)") (class "Default")
      (node (ref "C34") (pin "1") (pinfunction "1_1") (pintype "passive"))
      (node (ref "U3") (pin "5") (pinfunction "C2-_5") (pintype "passive"))
    )
    (net (code "74") (name "Net-(U3-R1IN)") (class "Default")
      (node (ref "U3") (pin "13") (pinfunction "R1IN_13") (pintype "passive"))
      (node (ref "X4") (pin "3") (pinfunction "3_3") (pintype "passive"))
    )
    (net (code "75") (name "Net-(U3-R1OUT)") (class "Default")
      (node (ref "U3") (pin "12") (pinfunction "R1OUT_12") (pintype "passive"))
      (node (ref "U7") (pin "3") (pinfunction "A1_3") (pintype "passive"))
    )
    (net (code "76") (name "Net-(U3-T1IN)") (class "Default")
      (node (ref "U3") (pin "11") (pinfunction "T1IN_11") (pintype "passive"))
      (node (ref "U6") (pin "14") (pinfunction "B1_14") (pintype "passive"))
    )
    (net (code "77") (name "Net-(U3-T1OUT)") (class "Default")
      (node (ref "U3") (pin "14") (pinfunction "T1OUT_14") (pintype "passive"))
      (node (ref "X4") (pin "2") (pinfunction "2_2") (pintype "passive"))
    )
    (net (code "78") (name "Net-(U3-V+)") (class "Default")
      (node (ref "C30") (pin "1") (pinfunction "1_1") (pintype "passive"))
      (node (ref "U3") (pin "2") (pinfunction "V+_2") (pintype "passive"))
    )
    (net (code "79") (name "Net-(U3-V-)") (class "Default")
      (node (ref "C31") (pin "2") (pinfunction "2_2") (pintype "passive"))
      (node (ref "U3") (pin "6") (pinfunction "V-_6") (pintype "passive"))
    )
    (net (code "80") (name "Net-(U7-A2)") (class "Default")
      (node (ref "C29") (pin "2") (pinfunction "2_2") (pintype "passive"))
      (node (ref "R20") (pin "1") (pinfunction "1_1") (pintype "passive"))
      (node (ref "R24") (pin "2") (pinfunction "2_2") (pintype "passive"))
      (node (ref "U7") (pin "4") (pinfunction "A2_4") (pintype "passive"))
    )
    (net (code "81") (name "Net-(U7-A3)") (class "Default")
      (node (ref "C28") (pin "2") (pinfunction "2_2") (pintype "passive"))
      (node (ref "R21") (pin "1") (pinfunction "1_1") (pintype "passive"))
      (node (ref "R23") (pin "2") (pinfunction "2_2") (pintype "passive"))
      (node (ref "U7") (pin "5") (pinfunction "A3_5") (pintype "passive"))
    )
    (net (code "82") (name "Net-(U8-CANH)") (class "Default")
      (node (ref "J2") (pin "1") (pinfunction "1_1") (pintype "passive"))
      (node (ref "U8") (pin "12") (pinfunction "CANH_12") (pintype "passive"))
      (node (ref "X10") (pin "1") (pinfunction "CANH_1") (pintype "passive"))
      (node (ref "X11") (pin "1") (pinfunction "CANH_1") (pintype "passive"))
    )
    (net (code "83") (name "Net-(U8-CANL)") (class "Default")
      (node (ref "R33") (pin "2") (pinfunction "2_2") (pintype "passive"))
      (node (ref "U8") (pin "11") (pinfunction "CANL_11") (pintype "passive"))
      (node (ref "X10") (pin "2") (pinfunction "CANL_2") (pintype "passive"))
      (node (ref "X11") (pin "2") (pinfunction "CANL_2") (pintype "passive"))
    )
    (net (code "84") (name "Net-(U9-DD+)") (class "Default")
      (node (ref "R29") (pin "2") (pinfunction "2_2") (pintype "passive"))
      (node (ref "U9") (pin "10") (pinfunction "DD+_10") (pintype "passive"))
    )
    (net (code "85") (name "Net-(U9-DD-)") (class "Default")
      (node (ref "R28") (pin "1") (pinfunction "1_1") (pintype "passive"))
      (node (ref "U9") (pin "11") (pinfunction "DD-_11") (pintype "passive"))
    )
    (net (code "86") (name "Net-(U9-PDEN)") (class "Default")
      (node (ref "C51") (pin "1") (pinfunction "1_1") (pintype "passive"))
      (node (ref "U9") (pin "3") (pinfunction "Vdd1_3") (pintype "passive"))
      (node (ref "U9") (pin "4") (pinfunction "PDEN_4") (pintype "passive"))
      (node (ref "U9") (pin "5") (pinfunction "SPU_5") (pintype "passive"))
    )
    (net (code "87") (name "Net-(U9-UD+)") (class "Default")
      (node (ref "R31") (pin "1") (pinfunction "1_1") (pintype "passive"))
      (node (ref "U9") (pin "7") (pinfunction "UD+_7") (pintype "passive"))
    )
    (net (code "88") (name "Net-(U9-UD-)") (class "Default")
      (node (ref "R30") (pin "2") (pinfunction "2_2") (pintype "passive"))
      (node (ref "U9") (pin "6") (pinfunction "UD-_6") (pintype "passive"))
    )
    (net (code "89") (name "Net-(U9-Vbus1)") (class "Default")
      (node (ref "C50") (pin "1") (pinfunction "1_1") (pintype "passive"))
      (node (ref "D10") (pin "1") (pinfunction "1_1") (pintype "passive"))
      (node (ref "U9") (pin "1") (pinfunction "Vbus1_1") (pintype "passive"))
      (node (ref "X12") (pin "1") (pinfunction "VBUS_1") (pintype "power_in"))
    )
    (net (code "90") (name "Net-(X12-D+)") (class "Default")
      (node (ref "R31") (pin "2") (pinfunction "2_2") (pintype "passive"))
      (node (ref "X12") (pin "3") (pinfunction "D+_3") (pintype "bidirectional"))
    )
    (net (code "91") (name "Net-(X12-D-)") (class "Default")
      (node (ref "R30") (pin "1") (pinfunction "1_1") (pintype "passive"))
      (node (ref "X12") (pin "2") (pinfunction "D-_2") (pintype "bidirectional"))
    )
    (net (code "92") (name "V5V") (class "Default")
      (node (ref "C41") (pin "2") (pinfunction "2_2") (pintype "passive"))
      (node (ref "C42") (pin "2") (pinfunction "2_2") (pintype "passive"))
      (node (ref "U4") (pin "2") (pinfunction "+Vin_2") (pintype "passive"))
      (node (ref "U5") (pin "2") (pinfunction "+Vin_2") (pintype "passive"))
      (node (ref "X7") (pin "13") (pinfunction "13_13") (pintype "passive"))
      (node (ref "X9") (pin "11") (pinfunction "11_11") (pintype "passive"))
      (node (ref "X9") (pin "12") (pinfunction "12_12") (pintype "passive"))
    )
    (net (code "93") (name "V15V") (class "Default")
      (node (ref "X7") (pin "15") (pinfunction "15_15") (pintype "passive"))
      (node (ref "X9") (pin "10") (pinfunction "10_10") (pintype "passive"))
      (node (ref "X9") (pin "9") (pinfunction "9_9") (pintype "passive"))
    )
    (net (code "94") (name "VDDC") (class "Default")
      (node (ref "C32") (pin "2") (pinfunction "2_2") (pintype "passive"))
      (node (ref "C39") (pin "1") (pinfunction "1_1") (pintype "passive"))
      (node (ref "C40") (pin "1") (pinfunction "1_1") (pintype "passive"))
      (node (ref "C43") (pin "2") (pinfunction "2_2") (pintype "passive"))
      (node (ref "C44") (pin "1") (pinfunction "1_1") (pintype "passive"))
      (node (ref "C45") (pin "1") (pinfunction "1_1") (pintype "passive"))
      (node (ref "D6") (pin "6") (pinfunction "VCC_6") (pintype "passive"))
      (node (ref "LCD1") (pin "7") (pinfunction "VDD_7") (pintype "passive"))
      (node (ref "R26") (pin "1") (pinfunction "1_1") (pintype "passive"))
      (node (ref "R27") (pin "1") (pinfunction "1_1") (pintype "passive"))
      (node (ref "R32") (pin "2") (pinfunction "2_2") (pintype "passive"))
      (node (ref "U10") (pin "5") (pinfunction "VCC_5") (pintype "power_in"))
      (node (ref "U6") (pin "1") (pinfunction "VDD1_1") (pintype "passive"))
      (node (ref "U7") (pin "16") (pinfunction "VDD2_16") (pintype "passive"))
      (node (ref "U8") (pin "7") (pinfunction "VDD1_7") (pintype "passive"))
      (node (ref "U9") (pin "13") (pinfunction "SPD_13") (pintype "passive"))
      (node (ref "U9") (pin "14") (pinfunction "Vdd2_14") (pintype "passive"))
      (node (ref "U9") (pin "16") (pinfunction "Vbus2_16") (pintype "passive"))
      (node (ref "X8") (pin "11") (pinfunction "11_11") (pintype "passive"))
      (node (ref "X9") (pin "13") (pinfunction "13_13") (pintype "passive"))
      (node (ref "X9") (pin "14") (pinfunction "14_14") (pintype "passive"))
    )
    (net (code "95") (name "unconnected-(U3-R2IN-Pad8)") (class "Default")
      (node (ref "U3") (pin "8") (pinfunction "R2IN_8") (pintype "passive"))
    )
    (net (code "96") (name "unconnected-(U3-R2OUT-Pad9)") (class "Default")
      (node (ref "U3") (pin "9") (pinfunction "R2OUT_9") (pintype "passive"))
    )
    (net (code "97") (name "unconnected-(U3-T2IN-Pad10)") (class "Default")
      (node (ref "U3") (pin "10") (pinfunction "T2IN_10") (pintype "passive"))
    )
    (net (code "98") (name "unconnected-(U3-T2OUT-Pad7)") (class "Default")
      (node (ref "U3") (pin "7") (pinfunction "T2OUT_7") (pintype "passive"))
    )
    (net (code "99") (name "unconnected-(U6-EN2-Pad10)") (class "Default")
      (node (ref "U6") (pin "10") (pinfunction "EN2_10") (pintype "passive"))
    )
    (net (code "100") (name "unconnected-(U6-NC-Pad7)") (class "Default")
      (node (ref "U6") (pin "7") (pinfunction "NC_7") (pintype "passive"))
    )
    (net (code "101") (name "unconnected-(U7-EN2-Pad10)") (class "Default")
      (node (ref "U7") (pin "10") (pinfunction "EN2_10") (pintype "passive"))
    )
    (net (code "102") (name "unconnected-(U7-NC-Pad7)") (class "Default")
      (node (ref "U7") (pin "7") (pinfunction "NC_7") (pintype "passive"))
    )
    (net (code "103") (name "unconnected-(U8-NC-Pad1)") (class "Default")
      (node (ref "U8") (pin "1") (pinfunction "NC_1") (pintype "passive"))
    )
    (net (code "104") (name "unconnected-(U8-NC-Pad14)") (class "Default")
      (node (ref "U8") (pin "14") (pinfunction "NC_14") (pintype "passive"))
    )
    (net (code "105") (name "unconnected-(U8-NC-Pad15)") (class "Default")
      (node (ref "U8") (pin "15") (pinfunction "NC_15") (pintype "passive"))
    )
    (net (code "106") (name "unconnected-(U8-VREF-Pad10)") (class "Default")
      (node (ref "U8") (pin "10") (pinfunction "VREF_10") (pintype "passive"))
    )
    (net (code "107") (name "unconnected-(X4-Pad1)") (class "Default")
      (node (ref "X4") (pin "1") (pinfunction "1_1") (pintype "passive"))
    )
    (net (code "108") (name "unconnected-(X4-Pad4)") (class "Default")
      (node (ref "X4") (pin "4") (pinfunction "4_4") (pintype "passive"))
    )
    (net (code "109") (name "unconnected-(X4-Pad6)") (class "Default")
      (node (ref "X4") (pin "6") (pinfunction "6_6") (pintype "passive"))
    )
    (net (code "110") (name "unconnected-(X4-Pad7)") (class "Default")
      (node (ref "X4") (pin "7") (pinfunction "7_7") (pintype "passive"))
    )
    (net (code "111") (name "unconnected-(X4-Pad8)") (class "Default")
      (node (ref "X4") (pin "8") (pinfunction "8_8") (pintype "passive"))
    )
    (net (code "112") (name "unconnected-(X4-Pad9)") (class "Default")
      (node (ref "X4") (pin "9") (pinfunction "9_9") (pintype "passive"))
    )
    (net (code "113") (name "unconnected-(X12-DI-Pad4)") (class "Default")
      (node (ref "X12") (pin "4") (pinfunction "DI_4") (pintype "bidirectional"))
    )
  )
)
